# power.net
KiCad netlist of a schematic drawn in Altium Designer
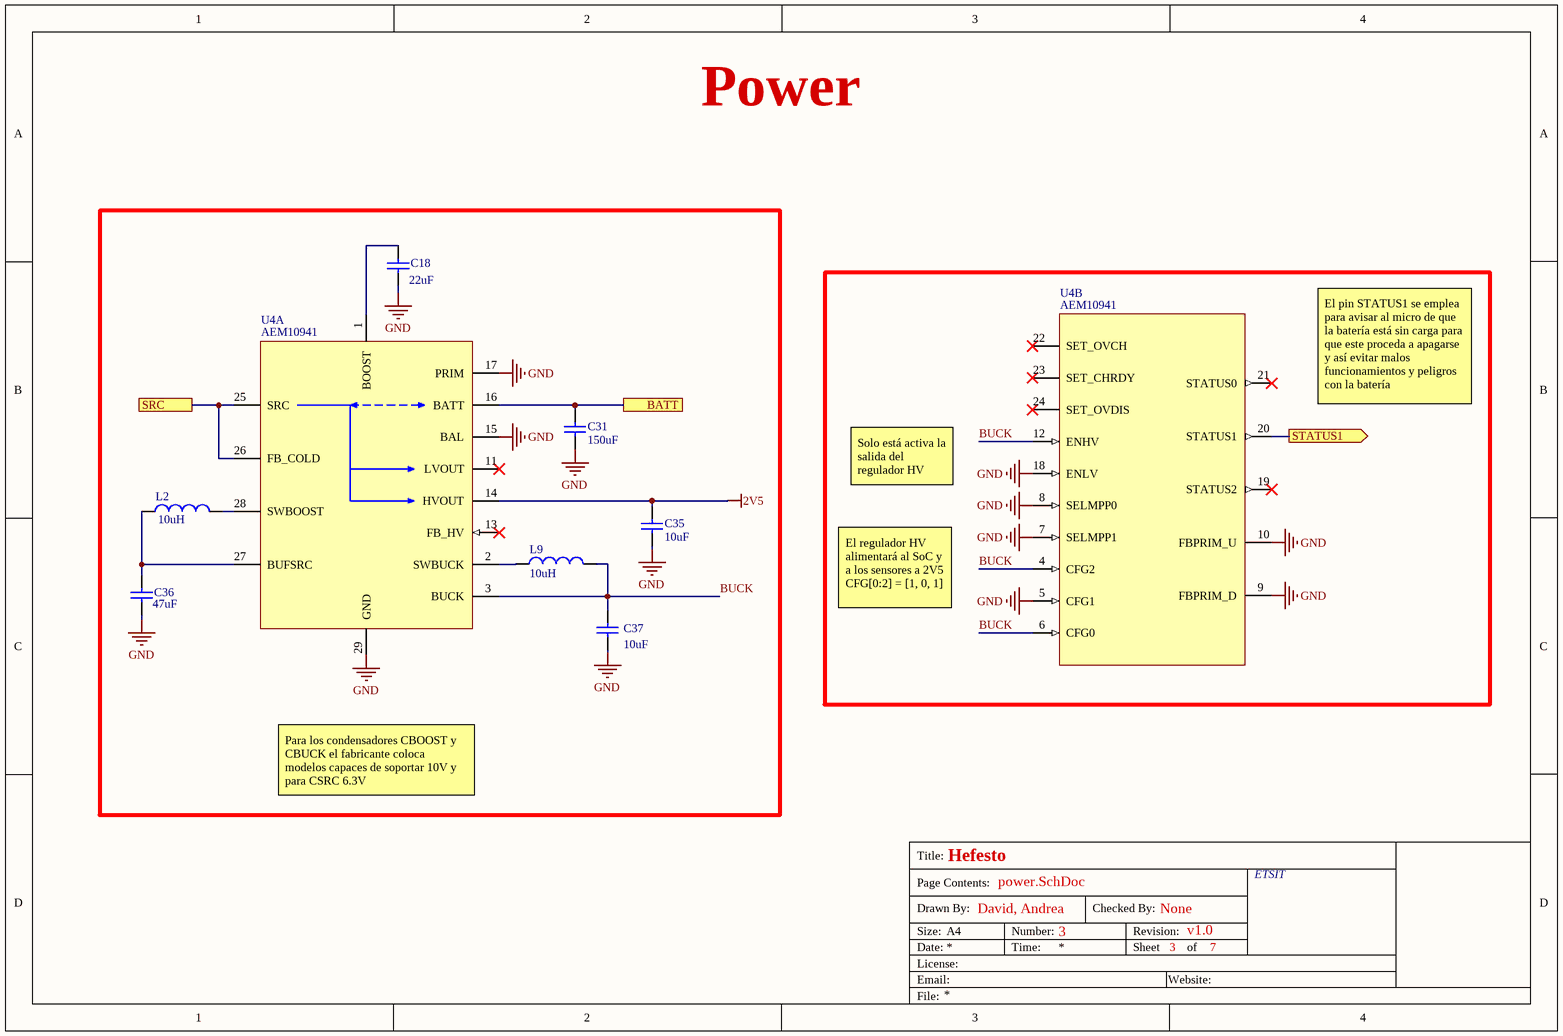
[diagram p0: power.SchDoc]

(export (version "E")
  (design (tool "Eeschema 10.0.6"))
  (components
    (comp (ref "C18")
      (value "22uF")
      (footprint "1608[0603]")
      (description "Capacitor (Semiconductor SIM Model)")
      (fields (field (name "Comment") "Cap Semi") (field (name "PUBLISHER") "Altium Limited"))
      (libsource (lib "Miscellaneous Devices") (part "Cap Semi"))
    )
    (comp (ref "C31")
      (value "150uF")
      (footprint "1608[0603]")
      (description "Capacitor (Semiconductor SIM Model)")
      (fields (field (name "PUBLISHER") "Altium Limited"))
      (libsource (lib "Miscellaneous Devices") (part "Cap Semi"))
    )
    (comp (ref "C35")
      (value "10uF")
      (footprint "1608[0603]")
      (description "Capacitor (Semiconductor SIM Model)")
      (fields (field (name "PUBLISHER") "Altium Limited"))
      (libsource (lib "Miscellaneous Devices") (part "Cap Semi"))
    )
    (comp (ref "C36")
      (value "47uF")
      (footprint "1608[0603]")
      (description "Capacitor (Semiconductor SIM Model)")
      (fields (field (name "Comment") "Cap Semi") (field (name "PUBLISHER") "Altium Limited"))
      (libsource (lib "Miscellaneous Devices") (part "Cap Semi"))
    )
    (comp (ref "C37")
      (value "10uF")
      (footprint "1608[0603]")
      (description "Capacitor (Semiconductor SIM Model)")
      (fields (field (name "PUBLISHER") "Altium Limited"))
      (libsource (lib "Miscellaneous Devices") (part "Cap Semi"))
    )
    (comp (ref "L2")
      (value "~")
      (footprint "0603")
      (description "Inductor")
      (fields (field (name "LBOOST") "10uH") (field (name "PUBLISHER") "Altium Limited"))
      (libsource (lib "Miscellaneous Devices") (part "Inductor"))
    )
    (comp (ref "L9")
      (value "~")
      (footprint "0603")
      (description "Inductor")
      (fields (field (name "LBOOST") "10uH") (field (name "PUBLISHER") "Altium Limited"))
      (libsource (lib "") (part "Inductor_1"))
    )
    (comp (ref "U4")
      (value "AEM10941")
      (footprint "AEM10941")
      (description "AEM10941 - Symbol QFN28")
      (libsource (lib "DEOP2023") (part "AEM10941"))
    )
  )
  (nets
    (net (code "1") (name "/BATT") (class "Default")
      (node (ref "C31") (pin "2") (pinfunction "2_2") (pintype "passive"))
      (node (ref "U4") (pin "16") (pinfunction "BATT_16") (pintype "power_in"))
    )
    (net (code "2") (name "/BUCK") (class "Default")
      (node (ref "C37") (pin "2") (pinfunction "2_2") (pintype "passive"))
      (node (ref "L9") (pin "1") (pinfunction "1_1") (pintype "passive"))
      (node (ref "U4") (pin "12") (pinfunction "ENHV_12") (pintype "input"))
      (node (ref "U4") (pin "3") (pinfunction "BUCK_3") (pintype "power_in"))
      (node (ref "U4") (pin "4") (pinfunction "CFG2_4") (pintype "input"))
      (node (ref "U4") (pin "6") (pinfunction "CFG0_6") (pintype "input"))
    )
    (net (code "3") (name "/SRC") (class "Default")
      (node (ref "U4") (pin "25") (pinfunction "SRC_25") (pintype "power_in"))
      (node (ref "U4") (pin "26") (pinfunction "FB_COLD_26") (pintype "passive"))
    )
    (net (code "4") (name "/STATUS1") (class "Default")
      (node (ref "U4") (pin "20") (pinfunction "STATUS1_20") (pintype "output"))
    )
    (net (code "5") (name "2V5") (class "Default")
      (node (ref "C35") (pin "2") (pinfunction "2_2") (pintype "passive"))
      (node (ref "U4") (pin "14") (pinfunction "HVOUT_14") (pintype "power_in"))
    )
    (net (code "6") (name "GND") (class "Default")
      (node (ref "C18") (pin "1") (pinfunction "1_1") (pintype "passive"))
      (node (ref "C31") (pin "1") (pinfunction "1_1") (pintype "passive"))
      (node (ref "C35") (pin "1") (pinfunction "1_1") (pintype "passive"))
      (node (ref "C36") (pin "1") (pinfunction "1_1") (pintype "passive"))
      (node (ref "C37") (pin "1") (pinfunction "1_1") (pintype "passive"))
      (node (ref "U4") (pin "10") (pinfunction "FBPRIM_U_10") (pintype "passive"))
      (node (ref "U4") (pin "15") (pinfunction "BAL_15") (pintype "power_in"))
      (node (ref "U4") (pin "17") (pinfunction "PRIM_17") (pintype "power_in"))
      (node (ref "U4") (pin "18") (pinfunction "ENLV_18") (pintype "input"))
      (node (ref "U4") (pin "29") (pinfunction "GND_29") (pintype "passive"))
      (node (ref "U4") (pin "5") (pinfunction "CFG1_5") (pintype "input"))
      (node (ref "U4") (pin "7") (pinfunction "SELMPP1_7") (pintype "input"))
      (node (ref "U4") (pin "8") (pinfunction "SELMPP0_8") (pintype "input"))
      (node (ref "U4") (pin "9") (pinfunction "FBPRIM_D_9") (pintype "passive"))
    )
    (net (code "7") (name "Net-(U4A-BOOST)") (class "Default")
      (node (ref "C18") (pin "2") (pinfunction "2_2") (pintype "passive"))
      (node (ref "U4") (pin "1") (pinfunction "BOOST_1") (pintype "power_in"))
    )
    (net (code "8") (name "Net-(U4A-BUFSRC)") (class "Default")
      (node (ref "C36") (pin "2") (pinfunction "2_2") (pintype "passive"))
      (node (ref "L2") (pin "1") (pinfunction "1_1") (pintype "passive"))
      (node (ref "U4") (pin "27") (pinfunction "BUFSRC_27") (pintype "power_in"))
    )
    (net (code "9") (name "Net-(U4A-SWBOOST)") (class "Default")
      (node (ref "L2") (pin "2") (pinfunction "2_2") (pintype "passive"))
      (node (ref "U4") (pin "28") (pinfunction "SWBOOST_28") (pintype "power_in"))
    )
    (net (code "10") (name "Net-(U4A-SWBUCK)") (class "Default")
      (node (ref "L9") (pin "2") (pinfunction "2_2") (pintype "passive"))
      (node (ref "U4") (pin "2") (pinfunction "SWBUCK_2") (pintype "power_in"))
    )
    (net (code "11") (name "unconnected-(U4A-FB_HV-Pad13)") (class "Default")
      (node (ref "U4") (pin "13") (pinfunction "FB_HV_13") (pintype "input+no_connect"))
    )
    (net (code "12") (name "unconnected-(U4A-LVOUT-Pad11)") (class "Default")
      (node (ref "U4") (pin "11") (pinfunction "LVOUT_11") (pintype "power_in+no_connect"))
    )
    (net (code "13") (name "unconnected-(U4B-SET_CHRDY-Pad23)") (class "Default")
      (node (ref "U4") (pin "23") (pinfunction "SET_CHRDY_23") (pintype "passive+no_connect"))
    )
    (net (code "14") (name "unconnected-(U4B-SET_OVCH-Pad22)") (class "Default")
      (node (ref "U4") (pin "22") (pinfunction "SET_OVCH_22") (pintype "passive+no_connect"))
    )
    (net (code "15") (name "unconnected-(U4B-SET_OVDIS-Pad24)") (class "Default")
      (node (ref "U4") (pin "24") (pinfunction "SET_OVDIS_24") (pintype "passive+no_connect"))
    )
    (net (code "16") (name "unconnected-(U4B-STATUS0-Pad21)") (class "Default")
      (node (ref "U4") (pin "21") (pinfunction "STATUS0_21") (pintype "output+no_connect"))
    )
    (net (code "17") (name "unconnected-(U4B-STATUS2-Pad19)") (class "Default")
      (node (ref "U4") (pin "19") (pinfunction "STATUS2_19") (pintype "output+no_connect"))
    )
  )
)
